# Control_Circuit.net
KiCad netlist of a schematic drawn in Altium Designer
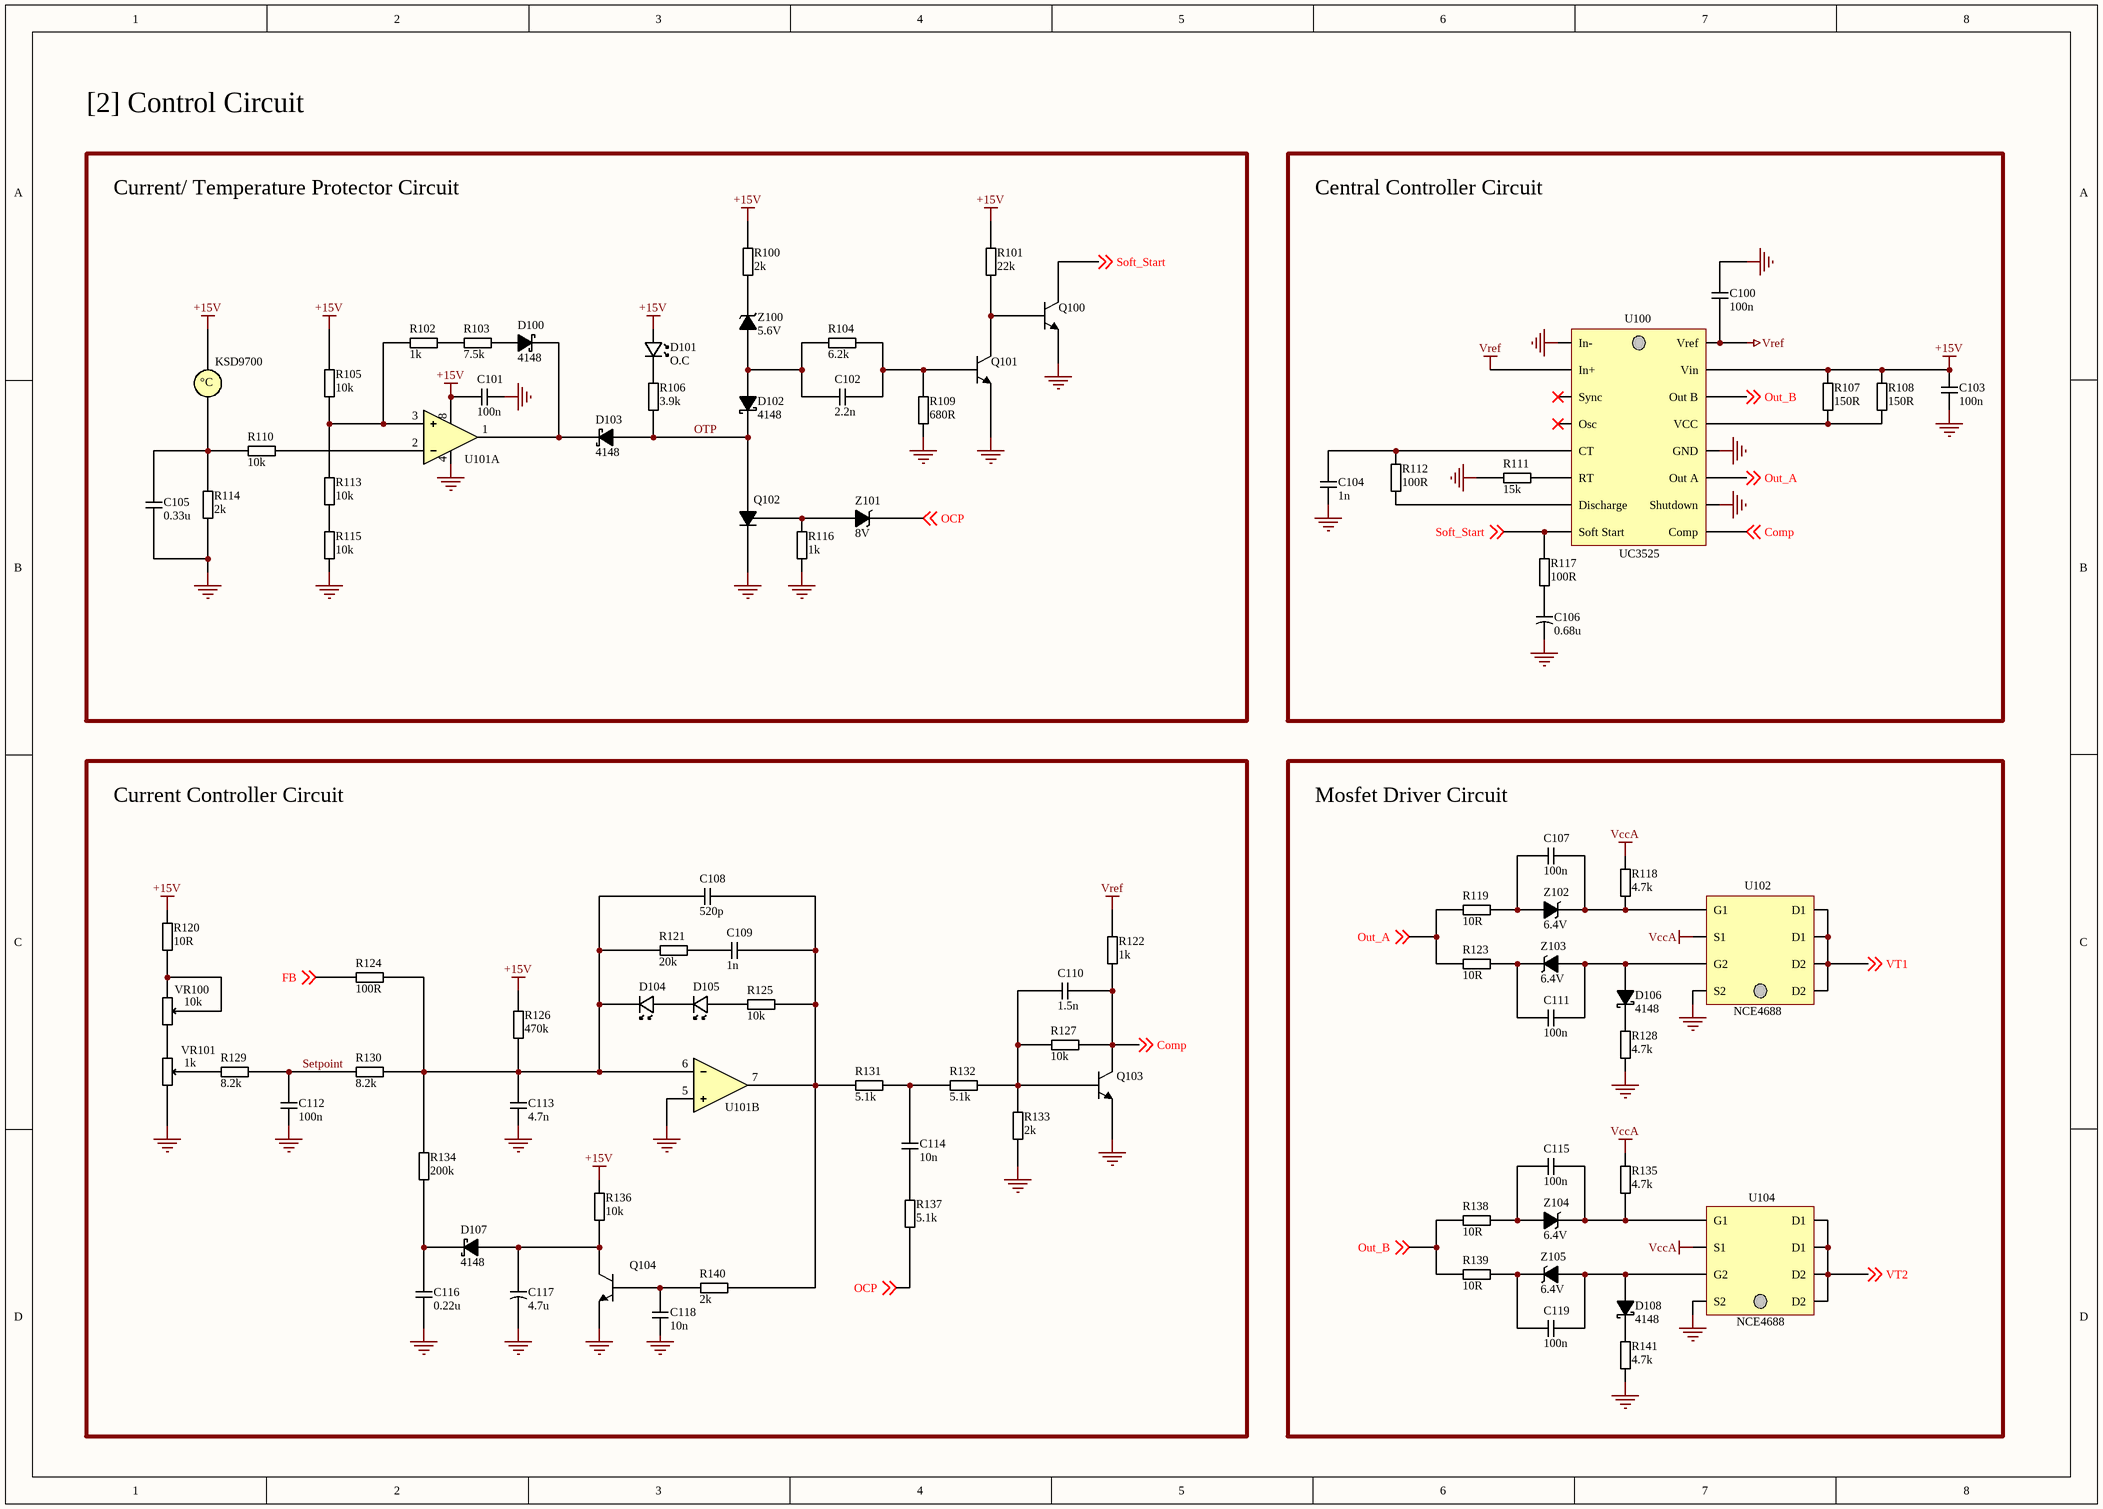
[diagram p0: Control_Circuit.SchDoc]

(export (version "E")
  (design (tool "Eeschema 10.0.6"))
  (components
    (comp (ref "C100")
      (value "100n")
      (footprint "Cap_SMD_0805")
      (description "0805 SMD Capacitor")
      (libsource (lib "LamThach_Sch_Lib") (part "Cap_SMD_0805"))
    )
    (comp (ref "C101")
      (value "100n")
      (footprint "Cap_SMD_0805")
      (description "0805 SMD Capacitor")
      (libsource (lib "LamThach_Sch_Lib") (part "Cap_SMD_0805"))
    )
    (comp (ref "C102")
      (value "2.2n")
      (footprint "Cap_SMD_0805")
      (description "0805 SMD Capacitor")
      (libsource (lib "LamThach_Sch_Lib") (part "Cap_SMD_0805"))
    )
    (comp (ref "C103")
      (value "100n")
      (footprint "Cap_SMD_0805")
      (description "0805 SMD Capacitor")
      (libsource (lib "LamThach_Sch_Lib") (part "Cap_SMD_0805"))
    )
    (comp (ref "C104")
      (value "1n")
      (footprint "Cap_SMD_0805")
      (description "0805 SMD Capacitor")
      (libsource (lib "LamThach_Sch_Lib") (part "Cap_SMD_0805"))
    )
    (comp (ref "C105")
      (value "0.33u")
      (footprint "Cap_SMD_0805")
      (description "0805 SMD Capacitor")
      (libsource (lib "LamThach_Sch_Lib") (part "Cap_SMD_0805"))
    )
    (comp (ref "C106")
      (value "0.68u")
      (footprint "Cap_THD_Tantalum_2.5mm")
      (fields (field (name "VOLTAGE") "V"))
      (libsource (lib "LamThach_Sch_Lib") (part "Cap_THD_Tantalum_2.5mm"))
    )
    (comp (ref "C107")
      (value "100n")
      (footprint "Cap_SMD_0805")
      (description "0805 SMD Capacitor")
      (libsource (lib "LamThach_Sch_Lib") (part "Cap_SMD_0805"))
    )
    (comp (ref "C108")
      (value "520p")
      (footprint "Cap_SMD_0805")
      (description "0805 SMD Capacitor")
      (libsource (lib "LamThach_Sch_Lib") (part "Cap_SMD_0805"))
    )
    (comp (ref "C109")
      (value "1n")
      (footprint "Cap_SMD_0805")
      (description "0805 SMD Capacitor")
      (libsource (lib "LamThach_Sch_Lib") (part "Cap_SMD_0805"))
    )
    (comp (ref "C110")
      (value "1.5n")
      (footprint "Cap_SMD_0805")
      (description "0805 SMD Capacitor")
      (libsource (lib "LamThach_Sch_Lib") (part "Cap_SMD_0805"))
    )
    (comp (ref "C111")
      (value "100n")
      (footprint "Cap_SMD_0805")
      (description "0805 SMD Capacitor")
      (libsource (lib "LamThach_Sch_Lib") (part "Cap_SMD_0805"))
    )
    (comp (ref "C112")
      (value "100n")
      (footprint "Cap_SMD_0805")
      (description "0805 SMD Capacitor")
      (libsource (lib "LamThach_Sch_Lib") (part "Cap_SMD_0805"))
    )
    (comp (ref "C113")
      (value "4.7n")
      (footprint "Cap_SMD_0805")
      (description "0805 SMD Capacitor")
      (libsource (lib "LamThach_Sch_Lib") (part "Cap_SMD_0805"))
    )
    (comp (ref "C114")
      (value "10n")
      (footprint "Cap_SMD_0805")
      (description "0805 SMD Capacitor")
      (libsource (lib "LamThach_Sch_Lib") (part "Cap_SMD_0805"))
    )
    (comp (ref "C115")
      (value "100n")
      (footprint "Cap_SMD_0805")
      (description "0805 SMD Capacitor")
      (libsource (lib "LamThach_Sch_Lib") (part "Cap_SMD_0805"))
    )
    (comp (ref "C116")
      (value "0.22u")
      (footprint "Cap_SMD_0805")
      (description "0805 SMD Capacitor")
      (libsource (lib "LamThach_Sch_Lib") (part "Cap_SMD_0805"))
    )
    (comp (ref "C117")
      (value "4.7u")
      (footprint "Cap_THD_Tantalum_2.5mm")
      (fields (field (name "VOLTAGE") "V"))
      (libsource (lib "") (part "Cap_THD_Tantalum_2.5mm_1"))
    )
    (comp (ref "C118")
      (value "10n")
      (footprint "Cap_SMD_0805")
      (description "0805 SMD Capacitor")
      (libsource (lib "LamThach_Sch_Lib") (part "Cap_SMD_0805"))
    )
    (comp (ref "C119")
      (value "100n")
      (footprint "Cap_SMD_0805")
      (description "0805 SMD Capacitor")
      (libsource (lib "LamThach_Sch_Lib") (part "Cap_SMD_0805"))
    )
    (comp (ref "D100")
      (value "4148")
      (footprint "Diode_SMD_4.8mm")
      (description "Schottky Diode")
      (libsource (lib "LamThach_Sch_Lib") (part "Diode_Schottky"))
    )
    (comp (ref "D101")
      (value "O.C")
      (footprint "Led_SMD_0805")
      (description "Light Emitting Diode - LED")
      (libsource (lib "LamThach_Sch_Lib") (part "Diode_LED"))
    )
    (comp (ref "D102")
      (value "4148")
      (footprint "Diode_SMD_4.8mm")
      (description "Schottky Diode")
      (libsource (lib "LamThach_Sch_Lib") (part "Diode_Schottky"))
    )
    (comp (ref "D103")
      (value "4148")
      (footprint "Diode_SMD_4.8mm")
      (description "Schottky Diode")
      (libsource (lib "LamThach_Sch_Lib") (part "Diode_Schottky"))
    )
    (comp (ref "D104")
      (value "D")
      (footprint "Led_SMD_0805")
      (libsource (lib "LamThach_Sch_Lib") (part "LED White"))
    )
    (comp (ref "D105")
      (value "D")
      (footprint "Led_SMD_0805")
      (libsource (lib "LamThach_Sch_Lib") (part "LED White"))
    )
    (comp (ref "D106")
      (value "4148")
      (footprint "Diode_SMD_4.8mm")
      (description "Schottky Diode")
      (libsource (lib "LamThach_Sch_Lib") (part "Diode_Schottky"))
    )
    (comp (ref "D107")
      (value "4148")
      (footprint "Diode_SMD_4.8mm")
      (description "Schottky Diode")
      (libsource (lib "LamThach_Sch_Lib") (part "Diode_Schottky"))
    )
    (comp (ref "D108")
      (value "4148")
      (footprint "Diode_SMD_4.8mm")
      (description "Schottky Diode")
      (libsource (lib "LamThach_Sch_Lib") (part "Diode_Schottky"))
    )
    (comp (ref "K100")
      (value "KSD9700")
      (footprint "CONN_XH_2P_2.5mm")
      (description "KSD-9700 series thermal protector")
      (libsource (lib "LamThach_Sch_Lib") (part "Relay_KSD9700"))
    )
    (comp (ref "Q100")
      (value "8050")
      (footprint "SOT23 - 2mm")
      (description "Bipolar Transistor BJT NPN Epitaxial Silicon 25V 1500mA 100MHz 1W TO-92-3")
      (fields
        (field (name "MANUFACTURER") "ON Semiconductor / Fairchild")
        (field (name "MANUFACTURER PART NUMBER") "SS8050DTA")
      )
      (libsource (lib "LamThach_Sch_Lib") (part "BJT_SS8050_V1"))
    )
    (comp (ref "Q101")
      (value "8050")
      (footprint "SOT23 - 2mm")
      (description "Bipolar Transistor BJT NPN Epitaxial Silicon 25V 1500mA 100MHz 1W TO-92-3")
      (fields
        (field (name "MANUFACTURER") "ON Semiconductor / Fairchild")
        (field (name "MANUFACTURER PART NUMBER") "SS8050DTA")
      )
      (libsource (lib "LamThach_Sch_Lib") (part "BJT_SS8050_V1"))
    )
    (comp (ref "Q102")
      (value "MCR100-6")
      (footprint "SOT23 - 2mm")
      (description "Thyristor SCR 400V 10A 3-Pin TO-92 Tape and Ammo")
      (fields
        (field (name "MANUFACTURER") "ON Semiconductor")
        (field (name "MANUFACTURER PART NUMBER") "MCR100-6ZL1G")
      )
      (libsource (lib "LamThach_Sch_Lib") (part "SCR_MCR100_6_V1"))
    )
    (comp (ref "Q103")
      (value "8050")
      (footprint "SOT23 - 2mm")
      (description "Bipolar Transistor BJT NPN Epitaxial Silicon 25V 1500mA 100MHz 1W TO-92-3")
      (fields
        (field (name "MANUFACTURER") "ON Semiconductor / Fairchild")
        (field (name "MANUFACTURER PART NUMBER") "SS8050DTA")
      )
      (libsource (lib "LamThach_Sch_Lib") (part "BJT_SS8050_V1"))
    )
    (comp (ref "Q104")
      (value "8050")
      (footprint "SOT23 - 2mm")
      (description "Bipolar Transistor BJT NPN Epitaxial Silicon 25V 1500mA 100MHz 1W TO-92-3")
      (fields
        (field (name "MANUFACTURER") "ON Semiconductor / Fairchild")
        (field (name "MANUFACTURER PART NUMBER") "SS8050DTA")
      )
      (libsource (lib "LamThach_Sch_Lib") (part "BJT_SS8050_V1"))
    )
    (comp (ref "R100")
      (value "2k")
      (footprint "Res_SMD_0805")
      (description "0805 SMD Resistor")
      (libsource (lib "LamThach_Sch_Lib") (part "Res_SMD_0805"))
    )
    (comp (ref "R101")
      (value "22k")
      (footprint "Res_SMD_0805")
      (description "0805 SMD Resistor")
      (libsource (lib "LamThach_Sch_Lib") (part "Res_SMD_0805"))
    )
    (comp (ref "R102")
      (value "1k")
      (footprint "Res_SMD_0805")
      (description "0805 SMD Resistor")
      (libsource (lib "LamThach_Sch_Lib") (part "Res_SMD_0805"))
    )
    (comp (ref "R103")
      (value "7.5k")
      (footprint "Res_SMD_0805")
      (description "0805 SMD Resistor")
      (libsource (lib "LamThach_Sch_Lib") (part "Res_SMD_0805"))
    )
    (comp (ref "R104")
      (value "6.2k")
      (footprint "Res_SMD_0805")
      (description "0805 SMD Resistor")
      (libsource (lib "LamThach_Sch_Lib") (part "Res_SMD_0805"))
    )
    (comp (ref "R105")
      (value "10k")
      (footprint "Res_SMD_0805")
      (description "0805 SMD Resistor")
      (libsource (lib "LamThach_Sch_Lib") (part "Res_SMD_0805"))
    )
    (comp (ref "R106")
      (value "3.9k")
      (footprint "Res_SMD_0805")
      (description "0805 SMD Resistor")
      (libsource (lib "LamThach_Sch_Lib") (part "Res_SMD_0805"))
    )
    (comp (ref "R107")
      (value "150R")
      (footprint "Res_SMD_0805")
      (description "0805 SMD Resistor")
      (libsource (lib "LamThach_Sch_Lib") (part "Res_SMD_0805"))
    )
    (comp (ref "R108")
      (value "150R")
      (footprint "Res_SMD_0805")
      (description "0805 SMD Resistor")
      (libsource (lib "LamThach_Sch_Lib") (part "Res_SMD_0805"))
    )
    (comp (ref "R109")
      (value "680R")
      (footprint "Res_SMD_0805")
      (description "0805 SMD Resistor")
      (libsource (lib "LamThach_Sch_Lib") (part "Res_SMD_0805"))
    )
    (comp (ref "R110")
      (value "10k")
      (footprint "Res_SMD_0805")
      (description "0805 SMD Resistor")
      (libsource (lib "LamThach_Sch_Lib") (part "Res_SMD_0805"))
    )
    (comp (ref "R111")
      (value "15k")
      (footprint "Res_SMD_0805")
      (description "0805 SMD Resistor")
      (libsource (lib "LamThach_Sch_Lib") (part "Res_SMD_0805"))
    )
    (comp (ref "R112")
      (value "100R")
      (footprint "Res_SMD_0805")
      (description "0805 SMD Resistor")
      (libsource (lib "LamThach_Sch_Lib") (part "Res_SMD_0805"))
    )
    (comp (ref "R113")
      (value "10k")
      (footprint "Res_SMD_0805")
      (description "0805 SMD Resistor")
      (libsource (lib "LamThach_Sch_Lib") (part "Res_SMD_0805"))
    )
    (comp (ref "R114")
      (value "2k")
      (footprint "Res_SMD_0805")
      (description "0805 SMD Resistor")
      (libsource (lib "LamThach_Sch_Lib") (part "Res_SMD_0805"))
    )
    (comp (ref "R115")
      (value "10k")
      (footprint "Res_SMD_0805")
      (description "0805 SMD Resistor")
      (libsource (lib "LamThach_Sch_Lib") (part "Res_SMD_0805"))
    )
    (comp (ref "R116")
      (value "1k")
      (footprint "Res_SMD_0805")
      (description "0805 SMD Resistor")
      (libsource (lib "LamThach_Sch_Lib") (part "Res_SMD_0805"))
    )
    (comp (ref "R117")
      (value "100R")
      (footprint "Res_SMD_0805")
      (description "0805 SMD Resistor")
      (libsource (lib "LamThach_Sch_Lib") (part "Res_SMD_0805"))
    )
    (comp (ref "R118")
      (value "4.7k")
      (footprint "Res_SMD_0805")
      (description "0805 SMD Resistor")
      (libsource (lib "LamThach_Sch_Lib") (part "Res_SMD_0805"))
    )
    (comp (ref "R119")
      (value "10R")
      (footprint "Res_SMD_0805")
      (description "0805 SMD Resistor")
      (libsource (lib "LamThach_Sch_Lib") (part "Res_SMD_0805"))
    )
    (comp (ref "R120")
      (value "10R")
      (footprint "Res_SMD_0805")
      (description "0805 SMD Resistor")
      (libsource (lib "LamThach_Sch_Lib") (part "Res_SMD_0805"))
    )
    (comp (ref "R121")
      (value "20k")
      (footprint "Res_SMD_0805")
      (description "0805 SMD Resistor")
      (libsource (lib "LamThach_Sch_Lib") (part "Res_SMD_0805"))
    )
    (comp (ref "R122")
      (value "1k")
      (footprint "Res_SMD_0805")
      (description "0805 SMD Resistor")
      (libsource (lib "LamThach_Sch_Lib") (part "Res_SMD_0805"))
    )
    (comp (ref "R123")
      (value "10R")
      (footprint "Res_SMD_0805")
      (description "0805 SMD Resistor")
      (libsource (lib "LamThach_Sch_Lib") (part "Res_SMD_0805"))
    )
    (comp (ref "R124")
      (value "100R")
      (footprint "Res_SMD_0805")
      (description "0805 SMD Resistor")
      (libsource (lib "LamThach_Sch_Lib") (part "Res_SMD_0805"))
    )
    (comp (ref "R125")
      (value "10k")
      (footprint "Res_SMD_0805")
      (description "0805 SMD Resistor")
      (libsource (lib "LamThach_Sch_Lib") (part "Res_SMD_0805"))
    )
    (comp (ref "R126")
      (value "470k")
      (footprint "Res_SMD_0805")
      (description "0805 SMD Resistor")
      (libsource (lib "LamThach_Sch_Lib") (part "Res_SMD_0805"))
    )
    (comp (ref "R127")
      (value "10k")
      (footprint "Res_SMD_0805")
      (description "0805 SMD Resistor")
      (libsource (lib "LamThach_Sch_Lib") (part "Res_SMD_0805"))
    )
    (comp (ref "R128")
      (value "4.7k")
      (footprint "Res_SMD_0805")
      (description "0805 SMD Resistor")
      (libsource (lib "LamThach_Sch_Lib") (part "Res_SMD_0805"))
    )
    (comp (ref "R129")
      (value "8.2k")
      (footprint "Res_SMD_0805")
      (description "0805 SMD Resistor")
      (libsource (lib "LamThach_Sch_Lib") (part "Res_SMD_0805"))
    )
    (comp (ref "R130")
      (value "8.2k")
      (footprint "Res_SMD_0805")
      (description "0805 SMD Resistor")
      (libsource (lib "LamThach_Sch_Lib") (part "Res_SMD_0805"))
    )
    (comp (ref "R131")
      (value "5.1k")
      (footprint "Res_SMD_0805")
      (description "0805 SMD Resistor")
      (libsource (lib "LamThach_Sch_Lib") (part "Res_SMD_0805"))
    )
    (comp (ref "R132")
      (value "5.1k")
      (footprint "Res_SMD_0805")
      (description "0805 SMD Resistor")
      (libsource (lib "LamThach_Sch_Lib") (part "Res_SMD_0805"))
    )
    (comp (ref "R133")
      (value "2k")
      (footprint "Res_SMD_0805")
      (description "0805 SMD Resistor")
      (libsource (lib "LamThach_Sch_Lib") (part "Res_SMD_0805"))
    )
    (comp (ref "R134")
      (value "200k")
      (footprint "Res_SMD_0805")
      (description "0805 SMD Resistor")
      (libsource (lib "LamThach_Sch_Lib") (part "Res_SMD_0805"))
    )
    (comp (ref "R135")
      (value "4.7k")
      (footprint "Res_SMD_0805")
      (description "0805 SMD Resistor")
      (libsource (lib "LamThach_Sch_Lib") (part "Res_SMD_0805"))
    )
    (comp (ref "R136")
      (value "10k")
      (footprint "Res_SMD_0805")
      (description "0805 SMD Resistor")
      (libsource (lib "LamThach_Sch_Lib") (part "Res_SMD_0805"))
    )
    (comp (ref "R137")
      (value "5.1k")
      (footprint "Res_SMD_0805")
      (description "0805 SMD Resistor")
      (libsource (lib "LamThach_Sch_Lib") (part "Res_SMD_0805"))
    )
    (comp (ref "R138")
      (value "10R")
      (footprint "Res_SMD_0805")
      (description "0805 SMD Resistor")
      (libsource (lib "LamThach_Sch_Lib") (part "Res_SMD_0805"))
    )
    (comp (ref "R139")
      (value "10R")
      (footprint "Res_SMD_0805")
      (description "0805 SMD Resistor")
      (libsource (lib "LamThach_Sch_Lib") (part "Res_SMD_0805"))
    )
    (comp (ref "R140")
      (value "2k")
      (footprint "Res_SMD_0805")
      (description "0805 SMD Resistor")
      (libsource (lib "LamThach_Sch_Lib") (part "Res_SMD_0805"))
    )
    (comp (ref "R141")
      (value "4.7k")
      (footprint "Res_SMD_0805")
      (description "0805 SMD Resistor")
      (libsource (lib "LamThach_Sch_Lib") (part "Res_SMD_0805"))
    )
    (comp (ref "U100")
      (value "UC3525")
      (footprint "SOP16")
      (description "Enhanced 35V, Dual 0.4A 400KHz PWM controller with Low output when off, 0C to 70C 16-PDIP 0 to 70")
      (fields
        (field (name "MANUFACTURER") "Texas Instruments")
        (field (name "MANUFACTURER PART NUMBER") "UC3525BN")
      )
      (libsource (lib "LamThach_Sch_Lib") (part "PMIC_UC3525"))
    )
    (comp (ref "U101")
      (value "OPAMP_LM358_V1")
      (footprint "SOP8")
      (libsource (lib "LamThach_Sch_Lib") (part "OPAMP_LM358_V1"))
    )
    (comp (ref "U102")
      (value "NCE4688")
      (footprint "SOP8")
      (description "Mosfet Gate Driver")
      (libsource (lib "LamThach_Sch_Lib") (part "PMIC_NCE4688"))
    )
    (comp (ref "U104")
      (value "NCE4688")
      (footprint "SOP8")
      (description "Mosfet Gate Driver")
      (libsource (lib "LamThach_Sch_Lib") (part "PMIC_NCE4688"))
    )
    (comp (ref "VR100")
      (value "10k")
      (footprint "Trimmer_2.54mm")
      (libsource (lib "LamThach_Sch_Lib") (part "Trimmer"))
    )
    (comp (ref "VR101")
      (value "1k")
      (footprint "Trimmer_2.54mm")
      (libsource (lib "LamThach_Sch_Lib") (part "Trimmer"))
    )
    (comp (ref "Z100")
      (value "5.6V")
      (footprint "Diode_SMD_4.8mm")
      (description "Zener Diode")
      (libsource (lib "LamThach_Sch_Lib") (part "Diode_Zener"))
    )
    (comp (ref "Z101")
      (value "8V")
      (footprint "Diode_SMD_4.8mm")
      (description "Zener Diode")
      (libsource (lib "LamThach_Sch_Lib") (part "Diode_Zener"))
    )
    (comp (ref "Z102")
      (value "6.4V")
      (footprint "Diode_SMD_4.8mm")
      (description "Zener Diode")
      (libsource (lib "LamThach_Sch_Lib") (part "Diode_Zener"))
    )
    (comp (ref "Z103")
      (value "6.4V")
      (footprint "Diode_SMD_4.8mm")
      (description "Zener Diode")
      (libsource (lib "LamThach_Sch_Lib") (part "Diode_Zener"))
    )
    (comp (ref "Z104")
      (value "6.4V")
      (footprint "Diode_SMD_4.8mm")
      (description "Zener Diode")
      (libsource (lib "LamThach_Sch_Lib") (part "Diode_Zener"))
    )
    (comp (ref "Z105")
      (value "6.4V")
      (footprint "Diode_SMD_4.8mm")
      (description "Zener Diode")
      (libsource (lib "LamThach_Sch_Lib") (part "Diode_Zener"))
    )
  )
  (nets
    (net (code "1") (name "+15V") (class "Default")
      (node (ref "C101") (pin "2") (pinfunction "2_2") (pintype "passive"))
      (node (ref "C103") (pin "2") (pinfunction "2_2") (pintype "passive"))
      (node (ref "D101") (pin "1") (pinfunction "A_1") (pintype "passive"))
      (node (ref "K100") (pin "1") (pinfunction "1_1") (pintype "passive"))
      (node (ref "R100") (pin "2") (pinfunction "2_2") (pintype "passive"))
      (node (ref "R101") (pin "2") (pinfunction "2_2") (pintype "passive"))
      (node (ref "R105") (pin "1") (pinfunction "1_1") (pintype "passive"))
      (node (ref "R107") (pin "2") (pinfunction "2_2") (pintype "passive"))
      (node (ref "R108") (pin "2") (pinfunction "2_2") (pintype "passive"))
      (node (ref "R120") (pin "2") (pinfunction "2_2") (pintype "passive"))
      (node (ref "R126") (pin "2") (pinfunction "2_2") (pintype "passive"))
      (node (ref "R136") (pin "2") (pinfunction "2_2") (pintype "passive"))
      (node (ref "U100") (pin "15") (pinfunction "Vin_15") (pintype "passive"))
      (node (ref "U101") (pin "8") (pinfunction "V+_8") (pintype "passive"))
    )
    (net (code "2") (name "/OTP") (class "Default")
      (node (ref "D102") (pin "2") (pinfunction "K_2") (pintype "passive"))
      (node (ref "D103") (pin "1") (pinfunction "A_1") (pintype "passive"))
      (node (ref "Q102") (pin "1") (pinfunction "A_1") (pintype "passive"))
      (node (ref "R106") (pin "2") (pinfunction "2_2") (pintype "passive"))
    )
    (net (code "3") (name "/Setpoint") (class "Default")
      (node (ref "C112") (pin "1") (pinfunction "1_1") (pintype "passive"))
      (node (ref "R129") (pin "1") (pinfunction "1_1") (pintype "passive"))
      (node (ref "R130") (pin "2") (pinfunction "2_2") (pintype "passive"))
    )
    (net (code "4") (name "Comp") (class "Default")
      (node (ref "C110") (pin "1") (pinfunction "1_1") (pintype "passive"))
      (node (ref "Q103") (pin "3") (pinfunction "C_3") (pintype "passive"))
      (node (ref "R122") (pin "1") (pinfunction "1_1") (pintype "passive"))
      (node (ref "R127") (pin "1") (pinfunction "1_1") (pintype "passive"))
      (node (ref "U100") (pin "9") (pinfunction "Comp_9") (pintype "passive"))
    )
    (net (code "5") (name "FB") (class "Default")
      (node (ref "R124") (pin "2") (pinfunction "2_2") (pintype "passive"))
    )
    (net (code "6") (name "GND") (class "Default")
      (node (ref "C100") (pin "2") (pinfunction "2_2") (pintype "passive"))
      (node (ref "C101") (pin "1") (pinfunction "1_1") (pintype "passive"))
      (node (ref "C103") (pin "1") (pinfunction "1_1") (pintype "passive"))
      (node (ref "C104") (pin "1") (pinfunction "1_1") (pintype "passive"))
      (node (ref "C105") (pin "2") (pinfunction "2_2") (pintype "passive"))
      (node (ref "C106") (pin "2") (pinfunction "-_2") (pintype "passive"))
      (node (ref "C112") (pin "2") (pinfunction "2_2") (pintype "passive"))
      (node (ref "C113") (pin "2") (pinfunction "2_2") (pintype "passive"))
      (node (ref "C116") (pin "2") (pinfunction "2_2") (pintype "passive"))
      (node (ref "C117") (pin "2") (pinfunction "-_2") (pintype "passive"))
      (node (ref "C118") (pin "2") (pinfunction "2_2") (pintype "passive"))
      (node (ref "Q100") (pin "1") (pinfunction "E_1") (pintype "passive"))
      (node (ref "Q101") (pin "1") (pinfunction "E_1") (pintype "passive"))
      (node (ref "Q102") (pin "2") (pinfunction "K_2") (pintype "passive"))
      (node (ref "Q103") (pin "1") (pinfunction "E_1") (pintype "passive"))
      (node (ref "Q104") (pin "1") (pinfunction "E_1") (pintype "passive"))
      (node (ref "R109") (pin "1") (pinfunction "1_1") (pintype "passive"))
      (node (ref "R111") (pin "1") (pinfunction "1_1") (pintype "passive"))
      (node (ref "R114") (pin "1") (pinfunction "1_1") (pintype "passive"))
      (node (ref "R115") (pin "2") (pinfunction "2_2") (pintype "passive"))
      (node (ref "R116") (pin "1") (pinfunction "1_1") (pintype "passive"))
      (node (ref "R128") (pin "2") (pinfunction "2_2") (pintype "passive"))
      (node (ref "R133") (pin "2") (pinfunction "2_2") (pintype "passive"))
      (node (ref "R141") (pin "2") (pinfunction "2_2") (pintype "passive"))
      (node (ref "U100") (pin "1") (pinfunction "In-_1") (pintype "passive"))
      (node (ref "U100") (pin "10") (pinfunction "Shutdown_10") (pintype "passive"))
      (node (ref "U100") (pin "12") (pinfunction "GND_12") (pintype "passive"))
      (node (ref "U101") (pin "4") (pinfunction "V-_4") (pintype "passive"))
      (node (ref "U101") (pin "5") (pinfunction "In2+_5") (pintype "passive"))
      (node (ref "U102") (pin "1") (pinfunction "S2_1") (pintype "passive"))
      (node (ref "U104") (pin "1") (pinfunction "S2_1") (pintype "passive"))
      (node (ref "VR101") (pin "3") (pinfunction "3_3") (pintype "passive"))
    )
    (net (code "7") (name "Net-(C105-Pad1)") (class "Default")
      (node (ref "C105") (pin "1") (pinfunction "1_1") (pintype "passive"))
      (node (ref "K100") (pin "2") (pinfunction "2_2") (pintype "passive"))
      (node (ref "R110") (pin "1") (pinfunction "1_1") (pintype "passive"))
      (node (ref "R114") (pin "2") (pinfunction "2_2") (pintype "passive"))
    )
    (net (code "8") (name "Net-(C106-+)") (class "Default")
      (node (ref "C106") (pin "1") (pinfunction "+_1") (pintype "passive"))
      (node (ref "R117") (pin "1") (pinfunction "1_1") (pintype "passive"))
    )
    (net (code "9") (name "Net-(C109-Pad2)") (class "Default")
      (node (ref "C109") (pin "2") (pinfunction "2_2") (pintype "passive"))
      (node (ref "R121") (pin "2") (pinfunction "2_2") (pintype "passive"))
    )
    (net (code "10") (name "Net-(C114-Pad1)") (class "Default")
      (node (ref "C114") (pin "1") (pinfunction "1_1") (pintype "passive"))
      (node (ref "R137") (pin "2") (pinfunction "2_2") (pintype "passive"))
    )
    (net (code "11") (name "Net-(C114-Pad2)") (class "Default")
      (node (ref "C114") (pin "2") (pinfunction "2_2") (pintype "passive"))
      (node (ref "R131") (pin "2") (pinfunction "2_2") (pintype "passive"))
      (node (ref "R132") (pin "1") (pinfunction "1_1") (pintype "passive"))
    )
    (net (code "12") (name "Net-(C117-+)") (class "Default")
      (node (ref "C117") (pin "1") (pinfunction "+_1") (pintype "passive"))
      (node (ref "D107") (pin "1") (pinfunction "A_1") (pintype "passive"))
      (node (ref "Q104") (pin "3") (pinfunction "C_3") (pintype "passive"))
      (node (ref "R136") (pin "1") (pinfunction "1_1") (pintype "passive"))
    )
    (net (code "13") (name "Net-(D100-A)") (class "Default")
      (node (ref "D100") (pin "1") (pinfunction "A_1") (pintype "passive"))
      (node (ref "R103") (pin "2") (pinfunction "2_2") (pintype "passive"))
    )
    (net (code "14") (name "Net-(D100-K)") (class "Default")
      (node (ref "D100") (pin "2") (pinfunction "K_2") (pintype "passive"))
      (node (ref "D103") (pin "2") (pinfunction "K_2") (pintype "passive"))
      (node (ref "U101") (pin "1") (pinfunction "Out1_1") (pintype "passive"))
    )
    (net (code "15") (name "Net-(D101-K)") (class "Default")
      (node (ref "D101") (pin "2") (pinfunction "K_2") (pintype "passive"))
      (node (ref "R106") (pin "1") (pinfunction "1_1") (pintype "passive"))
    )
    (net (code "16") (name "Net-(D102-A)") (class "Default")
      (node (ref "C102") (pin "2") (pinfunction "2_2") (pintype "passive"))
      (node (ref "D102") (pin "1") (pinfunction "A_1") (pintype "passive"))
      (node (ref "R104") (pin "2") (pinfunction "2_2") (pintype "passive"))
      (node (ref "Z100") (pin "1") (pinfunction "A_1") (pintype "passive"))
    )
    (net (code "17") (name "Net-(D104-A)") (class "Default")
      (node (ref "D104") (pin "2") (pinfunction "A_2") (pintype "passive"))
      (node (ref "D105") (pin "1") (pinfunction "K_1") (pintype "passive"))
    )
    (net (code "18") (name "Net-(D104-K)") (class "Default")
      (node (ref "C108") (pin "2") (pinfunction "2_2") (pintype "passive"))
      (node (ref "C113") (pin "1") (pinfunction "1_1") (pintype "passive"))
      (node (ref "D104") (pin "1") (pinfunction "K_1") (pintype "passive"))
      (node (ref "R121") (pin "1") (pinfunction "1_1") (pintype "passive"))
      (node (ref "R124") (pin "1") (pinfunction "1_1") (pintype "passive"))
      (node (ref "R126") (pin "1") (pinfunction "1_1") (pintype "passive"))
      (node (ref "R130") (pin "1") (pinfunction "1_1") (pintype "passive"))
      (node (ref "R134") (pin "2") (pinfunction "2_2") (pintype "passive"))
      (node (ref "U101") (pin "6") (pinfunction "In2-_6") (pintype "passive"))
    )
    (net (code "19") (name "Net-(D105-A)") (class "Default")
      (node (ref "D105") (pin "2") (pinfunction "A_2") (pintype "passive"))
      (node (ref "R125") (pin "1") (pinfunction "1_1") (pintype "passive"))
    )
    (net (code "20") (name "Net-(D106-A)") (class "Default")
      (node (ref "C111") (pin "1") (pinfunction "1_1") (pintype "passive"))
      (node (ref "D106") (pin "1") (pinfunction "A_1") (pintype "passive"))
      (node (ref "U102") (pin "2") (pinfunction "G2_2") (pintype "passive"))
      (node (ref "Z103") (pin "1") (pinfunction "A_1") (pintype "passive"))
    )
    (net (code "21") (name "Net-(D106-K)") (class "Default")
      (node (ref "D106") (pin "2") (pinfunction "K_2") (pintype "passive"))
      (node (ref "R128") (pin "1") (pinfunction "1_1") (pintype "passive"))
    )
    (net (code "22") (name "Net-(D107-K)") (class "Default")
      (node (ref "C116") (pin "1") (pinfunction "1_1") (pintype "passive"))
      (node (ref "D107") (pin "2") (pinfunction "K_2") (pintype "passive"))
      (node (ref "R134") (pin "1") (pinfunction "1_1") (pintype "passive"))
    )
    (net (code "23") (name "Net-(D108-A)") (class "Default")
      (node (ref "C119") (pin "1") (pinfunction "1_1") (pintype "passive"))
      (node (ref "D108") (pin "1") (pinfunction "A_1") (pintype "passive"))
      (node (ref "U104") (pin "2") (pinfunction "G2_2") (pintype "passive"))
      (node (ref "Z105") (pin "1") (pinfunction "A_1") (pintype "passive"))
    )
    (net (code "24") (name "Net-(D108-K)") (class "Default")
      (node (ref "D108") (pin "2") (pinfunction "K_2") (pintype "passive"))
      (node (ref "R141") (pin "1") (pinfunction "1_1") (pintype "passive"))
    )
    (net (code "25") (name "Net-(Q100-B)") (class "Default")
      (node (ref "Q100") (pin "2") (pinfunction "B_2") (pintype "passive"))
      (node (ref "Q101") (pin "3") (pinfunction "C_3") (pintype "passive"))
      (node (ref "R101") (pin "1") (pinfunction "1_1") (pintype "passive"))
    )
    (net (code "26") (name "Net-(Q101-B)") (class "Default")
      (node (ref "C102") (pin "1") (pinfunction "1_1") (pintype "passive"))
      (node (ref "Q101") (pin "2") (pinfunction "B_2") (pintype "passive"))
      (node (ref "R104") (pin "1") (pinfunction "1_1") (pintype "passive"))
      (node (ref "R109") (pin "2") (pinfunction "2_2") (pintype "passive"))
    )
    (net (code "27") (name "Net-(Q102-G)") (class "Default")
      (node (ref "Q102") (pin "3") (pinfunction "G_3") (pintype "passive"))
      (node (ref "R116") (pin "2") (pinfunction "2_2") (pintype "passive"))
      (node (ref "Z101") (pin "1") (pinfunction "A_1") (pintype "passive"))
    )
    (net (code "28") (name "Net-(Q103-B)") (class "Default")
      (node (ref "C110") (pin "2") (pinfunction "2_2") (pintype "passive"))
      (node (ref "Q103") (pin "2") (pinfunction "B_2") (pintype "passive"))
      (node (ref "R127") (pin "2") (pinfunction "2_2") (pintype "passive"))
      (node (ref "R132") (pin "2") (pinfunction "2_2") (pintype "passive"))
      (node (ref "R133") (pin "1") (pinfunction "1_1") (pintype "passive"))
    )
    (net (code "29") (name "Net-(Q104-B)") (class "Default")
      (node (ref "C118") (pin "1") (pinfunction "1_1") (pintype "passive"))
      (node (ref "Q104") (pin "2") (pinfunction "B_2") (pintype "passive"))
      (node (ref "R140") (pin "2") (pinfunction "2_2") (pintype "passive"))
    )
    (net (code "30") (name "Net-(R102-Pad2)") (class "Default")
      (node (ref "R102") (pin "2") (pinfunction "2_2") (pintype "passive"))
      (node (ref "R103") (pin "1") (pinfunction "1_1") (pintype "passive"))
    )
    (net (code "31") (name "Net-(R113-Pad2)") (class "Default")
      (node (ref "R113") (pin "2") (pinfunction "2_2") (pintype "passive"))
      (node (ref "R115") (pin "1") (pinfunction "1_1") (pintype "passive"))
    )
    (net (code "32") (name "Net-(R120-Pad1)") (class "Default")
      (node (ref "R120") (pin "1") (pinfunction "1_1") (pintype "passive"))
      (node (ref "VR100") (pin "1") (pinfunction "1_1") (pintype "passive"))
      (node (ref "VR100") (pin "2") (pinfunction "2_2") (pintype "passive"))
    )
    (net (code "33") (name "Net-(R129-Pad2)") (class "Default")
      (node (ref "R129") (pin "2") (pinfunction "2_2") (pintype "passive"))
      (node (ref "VR101") (pin "2") (pinfunction "2_2") (pintype "passive"))
    )
    (net (code "34") (name "Net-(U100-CT)") (class "Default")
      (node (ref "C104") (pin "2") (pinfunction "2_2") (pintype "passive"))
      (node (ref "R112") (pin "2") (pinfunction "2_2") (pintype "passive"))
      (node (ref "U100") (pin "5") (pinfunction "CT_5") (pintype "passive"))
    )
    (net (code "35") (name "Net-(U100-Discharge)") (class "Default")
      (node (ref "R112") (pin "1") (pinfunction "1_1") (pintype "passive"))
      (node (ref "U100") (pin "7") (pinfunction "Discharge_7") (pintype "passive"))
    )
    (net (code "36") (name "Net-(U100-RT)") (class "Default")
      (node (ref "R111") (pin "2") (pinfunction "2_2") (pintype "passive"))
      (node (ref "U100") (pin "6") (pinfunction "RT_6") (pintype "passive"))
    )
    (net (code "37") (name "Net-(U100-VCC)") (class "Default")
      (node (ref "R107") (pin "1") (pinfunction "1_1") (pintype "passive"))
      (node (ref "R108") (pin "1") (pinfunction "1_1") (pintype "passive"))
      (node (ref "U100") (pin "13") (pinfunction "VCC_13") (pintype "passive"))
    )
    (net (code "38") (name "Net-(U101A-In1+)") (class "Default")
      (node (ref "R102") (pin "1") (pinfunction "1_1") (pintype "passive"))
      (node (ref "R105") (pin "2") (pinfunction "2_2") (pintype "passive"))
      (node (ref "R113") (pin "1") (pinfunction "1_1") (pintype "passive"))
      (node (ref "U101") (pin "3") (pinfunction "In1+_3") (pintype "passive"))
    )
    (net (code "39") (name "Net-(U101A-In1-)") (class "Default")
      (node (ref "R110") (pin "2") (pinfunction "2_2") (pintype "passive"))
      (node (ref "U101") (pin "2") (pinfunction "In1-_2") (pintype "passive"))
    )
    (net (code "40") (name "Net-(U101B-Out2)") (class "Default")
      (node (ref "C108") (pin "1") (pinfunction "1_1") (pintype "passive"))
      (node (ref "C109") (pin "1") (pinfunction "1_1") (pintype "passive"))
      (node (ref "R125") (pin "2") (pinfunction "2_2") (pintype "passive"))
      (node (ref "R131") (pin "1") (pinfunction "1_1") (pintype "passive"))
      (node (ref "R140") (pin "1") (pinfunction "1_1") (pintype "passive"))
      (node (ref "U101") (pin "7") (pinfunction "Out2_7") (pintype "passive"))
    )
    (net (code "41") (name "Net-(U102-G1)") (class "Default")
      (node (ref "C107") (pin "1") (pinfunction "1_1") (pintype "passive"))
      (node (ref "R118") (pin "1") (pinfunction "1_1") (pintype "passive"))
      (node (ref "U102") (pin "4") (pinfunction "G1_4") (pintype "passive"))
      (node (ref "Z102") (pin "2") (pinfunction "K_2") (pintype "passive"))
    )
    (net (code "42") (name "Net-(U104-G1)") (class "Default")
      (node (ref "C115") (pin "1") (pinfunction "1_1") (pintype "passive"))
      (node (ref "R135") (pin "2") (pinfunction "2_2") (pintype "passive"))
      (node (ref "U104") (pin "4") (pinfunction "G1_4") (pintype "passive"))
      (node (ref "Z104") (pin "2") (pinfunction "K_2") (pintype "passive"))
    )
    (net (code "43") (name "Net-(VR100-Pad3)") (class "Default")
      (node (ref "VR100") (pin "3") (pinfunction "3_3") (pintype "passive"))
      (node (ref "VR101") (pin "1") (pinfunction "1_1") (pintype "passive"))
    )
    (net (code "44") (name "Net-(Z100-K)") (class "Default")
      (node (ref "R100") (pin "1") (pinfunction "1_1") (pintype "passive"))
      (node (ref "Z100") (pin "2") (pinfunction "K_2") (pintype "passive"))
    )
    (net (code "45") (name "Net-(Z102-A)") (class "Default")
      (node (ref "C107") (pin "2") (pinfunction "2_2") (pintype "passive"))
      (node (ref "R119") (pin "2") (pinfunction "2_2") (pintype "passive"))
      (node (ref "Z102") (pin "1") (pinfunction "A_1") (pintype "passive"))
    )
    (net (code "46") (name "Net-(Z103-K)") (class "Default")
      (node (ref "C111") (pin "2") (pinfunction "2_2") (pintype "passive"))
      (node (ref "R123") (pin "2") (pinfunction "2_2") (pintype "passive"))
      (node (ref "Z103") (pin "2") (pinfunction "K_2") (pintype "passive"))
    )
    (net (code "47") (name "Net-(Z104-A)") (class "Default")
      (node (ref "C115") (pin "2") (pinfunction "2_2") (pintype "passive"))
      (node (ref "R138") (pin "2") (pinfunction "2_2") (pintype "passive"))
      (node (ref "Z104") (pin "1") (pinfunction "A_1") (pintype "passive"))
    )
    (net (code "48") (name "Net-(Z105-K)") (class "Default")
      (node (ref "C119") (pin "2") (pinfunction "2_2") (pintype "passive"))
      (node (ref "R139") (pin "2") (pinfunction "2_2") (pintype "passive"))
      (node (ref "Z105") (pin "2") (pinfunction "K_2") (pintype "passive"))
    )
    (net (code "49") (name "OCP") (class "Default")
      (node (ref "R137") (pin "1") (pinfunction "1_1") (pintype "passive"))
      (node (ref "Z101") (pin "2") (pinfunction "K_2") (pintype "passive"))
    )
    (net (code "50") (name "Out_A") (class "Default")
      (node (ref "R119") (pin "1") (pinfunction "1_1") (pintype "passive"))
      (node (ref "R123") (pin "1") (pinfunction "1_1") (pintype "passive"))
      (node (ref "U100") (pin "11") (pinfunction "Out_A_11") (pintype "passive"))
    )
    (net (code "51") (name "Out_B") (class "Default")
      (node (ref "R138") (pin "1") (pinfunction "1_1") (pintype "passive"))
      (node (ref "R139") (pin "1") (pinfunction "1_1") (pintype "passive"))
      (node (ref "U100") (pin "14") (pinfunction "Out_B_14") (pintype "passive"))
    )
    (net (code "52") (name "Soft_Start") (class "Default")
      (node (ref "Q100") (pin "3") (pinfunction "C_3") (pintype "passive"))
      (node (ref "R117") (pin "2") (pinfunction "2_2") (pintype "passive"))
      (node (ref "U100") (pin "8") (pinfunction "Soft_Start_8") (pintype "passive"))
    )
    (net (code "53") (name "VT1") (class "Default")
      (node (ref "U102") (pin "5") (pinfunction "D1_5") (pintype "passive"))
      (node (ref "U102") (pin "6") (pinfunction "D1_6") (pintype "passive"))
      (node (ref "U102") (pin "7") (pinfunction "D2_7") (pintype "passive"))
      (node (ref "U102") (pin "8") (pinfunction "D2_8") (pintype "passive"))
    )
    (net (code "54") (name "VT2") (class "Default")
      (node (ref "U104") (pin "5") (pinfunction "D1_5") (pintype "passive"))
      (node (ref "U104") (pin "6") (pinfunction "D1_6") (pintype "passive"))
      (node (ref "U104") (pin "7") (pinfunction "D2_7") (pintype "passive"))
      (node (ref "U104") (pin "8") (pinfunction "D2_8") (pintype "passive"))
    )
    (net (code "55") (name "VccA") (class "Default")
      (node (ref "R118") (pin "2") (pinfunction "2_2") (pintype "passive"))
      (node (ref "R135") (pin "1") (pinfunction "1_1") (pintype "passive"))
      (node (ref "U102") (pin "3") (pinfunction "S1_3") (pintype "passive"))
      (node (ref "U104") (pin "3") (pinfunction "S1_3") (pintype "passive"))
    )
    (net (code "56") (name "Vref") (class "Default")
      (node (ref "C100") (pin "1") (pinfunction "1_1") (pintype "passive"))
      (node (ref "R122") (pin "2") (pinfunction "2_2") (pintype "passive"))
      (node (ref "U100") (pin "16") (pinfunction "Vref_16") (pintype "passive"))
      (node (ref "U100") (pin "2") (pinfunction "In+_2") (pintype "passive"))
    )
    (net (code "57") (name "unconnected-(U100-Osc-Pad4)") (class "Default")
      (node (ref "U100") (pin "4") (pinfunction "Osc_4") (pintype "passive+no_connect"))
    )
    (net (code "58") (name "unconnected-(U100-Sync-Pad3)") (class "Default")
      (node (ref "U100") (pin "3") (pinfunction "Sync_3") (pintype "passive+no_connect"))
    )
  )
)
